# SD.net
KiCad netlist of a schematic drawn in Altium Designer
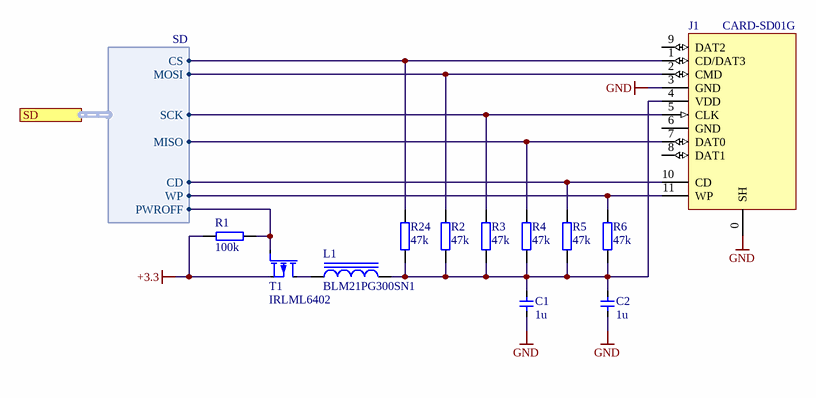
[diagram p0: SD.SchDoc]

(export (version "E")
  (design (tool "Eeschema 10.0.6"))
  (components
    (comp (ref "C1")
      (value "1u")
      (footprint "C0805")
      (description "C; capacitor")
      (libsource (lib "SONEL_all") (part "C"))
    )
    (comp (ref "C2")
      (value "1u")
      (footprint "C0805")
      (description "C; capacitor")
      (libsource (lib "SONEL_all") (part "C"))
    )
    (comp (ref "J1")
      (value "CARD-SD01G")
      (footprint "CARD-SD01G")
      (description "SD Card Socket, push-pull")
      (libsource (lib "sch") (part "SD"))
    )
    (comp (ref "L1")
      (value "BLM21PG300SN1")
      (footprint "L0805")
      (description "L;")
      (libsource (lib "SONEL_all") (part "BLM21PG300SN1"))
    )
    (comp (ref "R1")
      (value "100k")
      (footprint "R0805")
      (description "R; resistor")
      (libsource (lib "SONEL_all") (part "R"))
    )
    (comp (ref "R2")
      (value "47k")
      (footprint "R0805")
      (description "R; resistor")
      (libsource (lib "SONEL_all") (part "R"))
    )
    (comp (ref "R3")
      (value "47k")
      (footprint "R0805")
      (description "R; resistor")
      (libsource (lib "SONEL_all") (part "R"))
    )
    (comp (ref "R4")
      (value "47k")
      (footprint "R0805")
      (description "R; resistor")
      (libsource (lib "SONEL_all") (part "R"))
    )
    (comp (ref "R5")
      (value "47k")
      (footprint "R0805")
      (description "R; resistor")
      (libsource (lib "SONEL_all") (part "R"))
    )
    (comp (ref "R6")
      (value "47k")
      (footprint "R0805")
      (description "R; resistor")
      (libsource (lib "SONEL_all") (part "R"))
    )
    (comp (ref "R24")
      (value "47k")
      (footprint "R0805")
      (description "R; resistor")
      (libsource (lib "SONEL_all") (part "R"))
    )
    (comp (ref "T1")
      (value "IRLML6402")
      (footprint "MICRO3")
      (description "T_M_P; P-Channel MOSFET")
      (libsource (lib "SONEL_all") (part "IRLML6402"))
    )
  )
  (nets
    (net (code "2") (name "+3.3") (class "Default")
      (node (ref "R1") (pin "2") (pintype "passive"))
      (node (ref "T1") (pin "S") (pinfunction "S_S") (pintype "passive"))
    )
    (net (code "4") (name "GND") (class "Default")
      (node (ref "C1") (pin "1") (pintype "passive"))
      (node (ref "C2") (pin "1") (pintype "passive"))
      (node (ref "J1") (pin "0") (pinfunction "SH_0") (pintype "passive"))
      (node (ref "J1") (pin "3") (pinfunction "GND_3") (pintype "power_in"))
    )
    (net (code "5") (name "Net-(J1-CD)") (class "Default")
      (node (ref "J1") (pin "10") (pinfunction "CD_10") (pintype "passive"))
      (node (ref "R5") (pin "2") (pintype "passive"))
    )
    (net (code "6") (name "Net-(J1-CD{slash}DAT3)") (class "Default")
      (node (ref "J1") (pin "1") (pinfunction "CD/DAT3_1") (pintype "bidirectional"))
      (node (ref "R24") (pin "2") (pintype "passive"))
    )
    (net (code "7") (name "Net-(J1-CLK)") (class "Default")
      (node (ref "J1") (pin "5") (pinfunction "CLK_5") (pintype "input"))
      (node (ref "R3") (pin "2") (pintype "passive"))
    )
    (net (code "8") (name "Net-(J1-CMD)") (class "Default")
      (node (ref "J1") (pin "2") (pinfunction "CMD_2") (pintype "bidirectional"))
      (node (ref "R2") (pin "2") (pintype "passive"))
    )
    (net (code "9") (name "Net-(J1-DAT0)") (class "Default")
      (node (ref "J1") (pin "7") (pinfunction "DAT0_7") (pintype "bidirectional"))
      (node (ref "R4") (pin "2") (pintype "passive"))
    )
    (net (code "10") (name "Net-(J1-VDD)") (class "Default")
      (node (ref "C1") (pin "2") (pintype "passive"))
      (node (ref "C2") (pin "2") (pintype "passive"))
      (node (ref "J1") (pin "4") (pinfunction "VDD_4") (pintype "power_in"))
      (node (ref "L1") (pin "2") (pinfunction "2_2") (pintype "passive"))
      (node (ref "R2") (pin "1") (pintype "passive"))
      (node (ref "R24") (pin "1") (pintype "passive"))
      (node (ref "R3") (pin "1") (pintype "passive"))
      (node (ref "R4") (pin "1") (pintype "passive"))
      (node (ref "R5") (pin "1") (pintype "passive"))
      (node (ref "R6") (pin "1") (pintype "passive"))
    )
    (net (code "11") (name "Net-(J1-WP)") (class "Default")
      (node (ref "J1") (pin "11") (pinfunction "WP_11") (pintype "passive"))
      (node (ref "R6") (pin "2") (pintype "passive"))
    )
    (net (code "12") (name "Net-(L1-Pad1)") (class "Default")
      (node (ref "L1") (pin "1") (pinfunction "1_1") (pintype "passive"))
      (node (ref "T1") (pin "D") (pinfunction "D_D") (pintype "passive"))
    )
    (net (code "13") (name "Net-(R1-Pad1)") (class "Default")
      (node (ref "R1") (pin "1") (pintype "passive"))
      (node (ref "T1") (pin "G") (pinfunction "G_G") (pintype "passive"))
    )
    (net (code "14") (name "unconnected-(J1-DAT1-Pad8)") (class "Default")
      (node (ref "J1") (pin "8") (pinfunction "DAT1_8") (pintype "bidirectional"))
    )
    (net (code "15") (name "unconnected-(J1-DAT2-Pad9)") (class "Default")
      (node (ref "J1") (pin "9") (pinfunction "DAT2_9") (pintype "bidirectional"))
    )
    (net (code "16") (name "unconnected-(J1-GND-Pad6)") (class "Default")
      (node (ref "J1") (pin "6") (pinfunction "GND_6") (pintype "power_in"))
    )
  )
)
